# lcd_brd.net
KiCad netlist of a schematic drawn in EAGLE
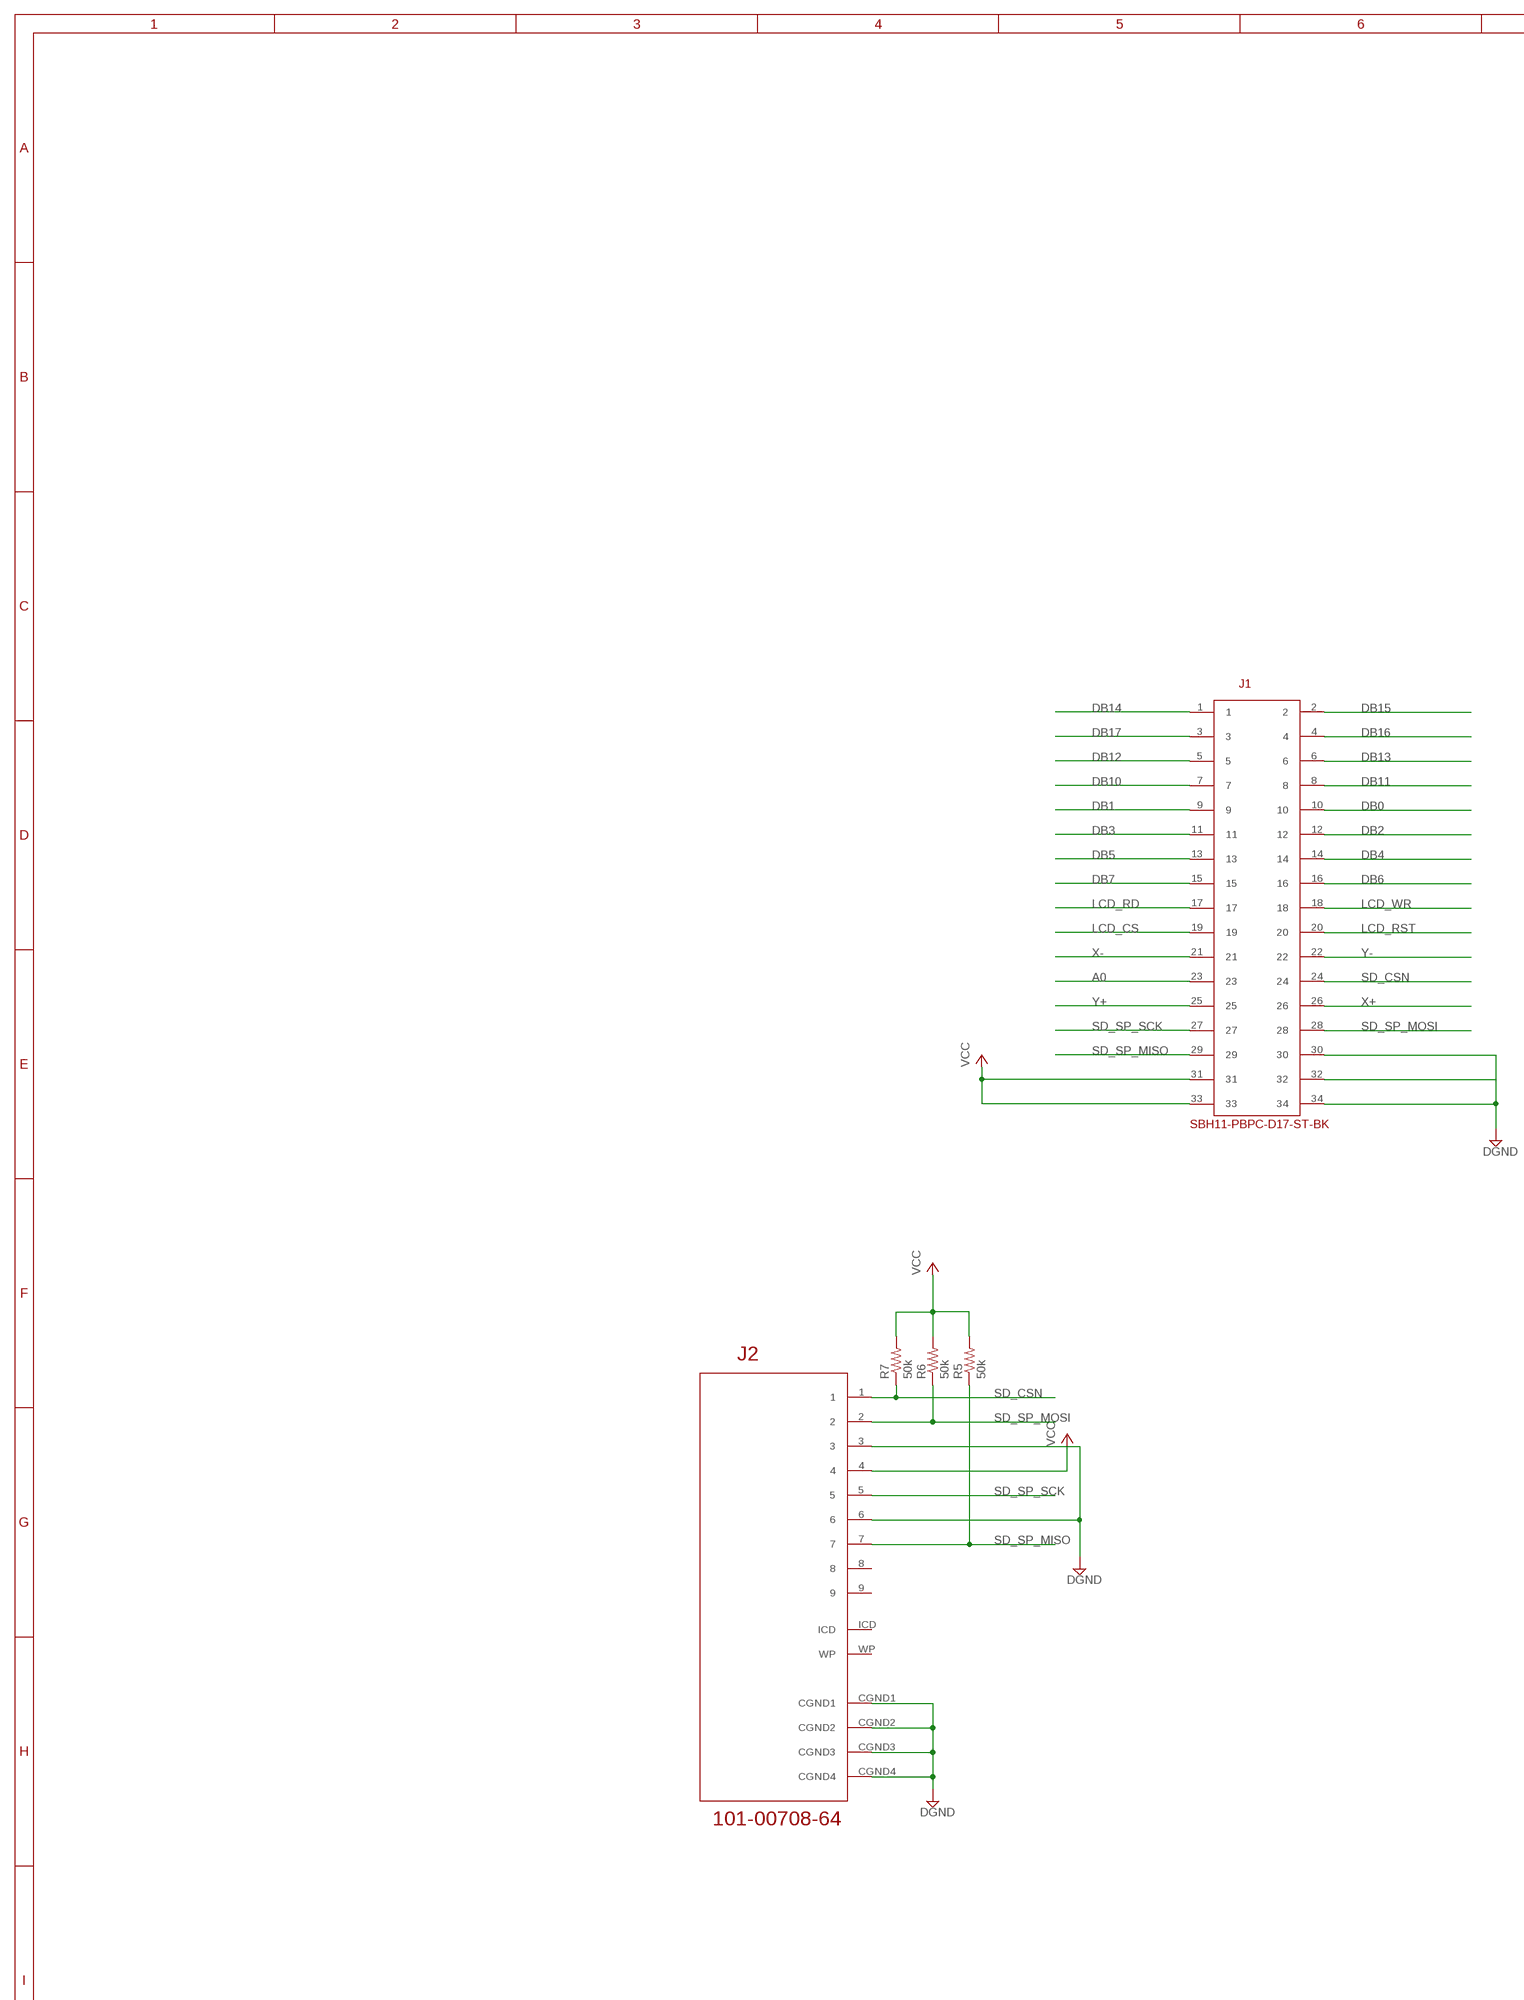
[diagram p0: schematic, sheet 1, part 1 of 2]
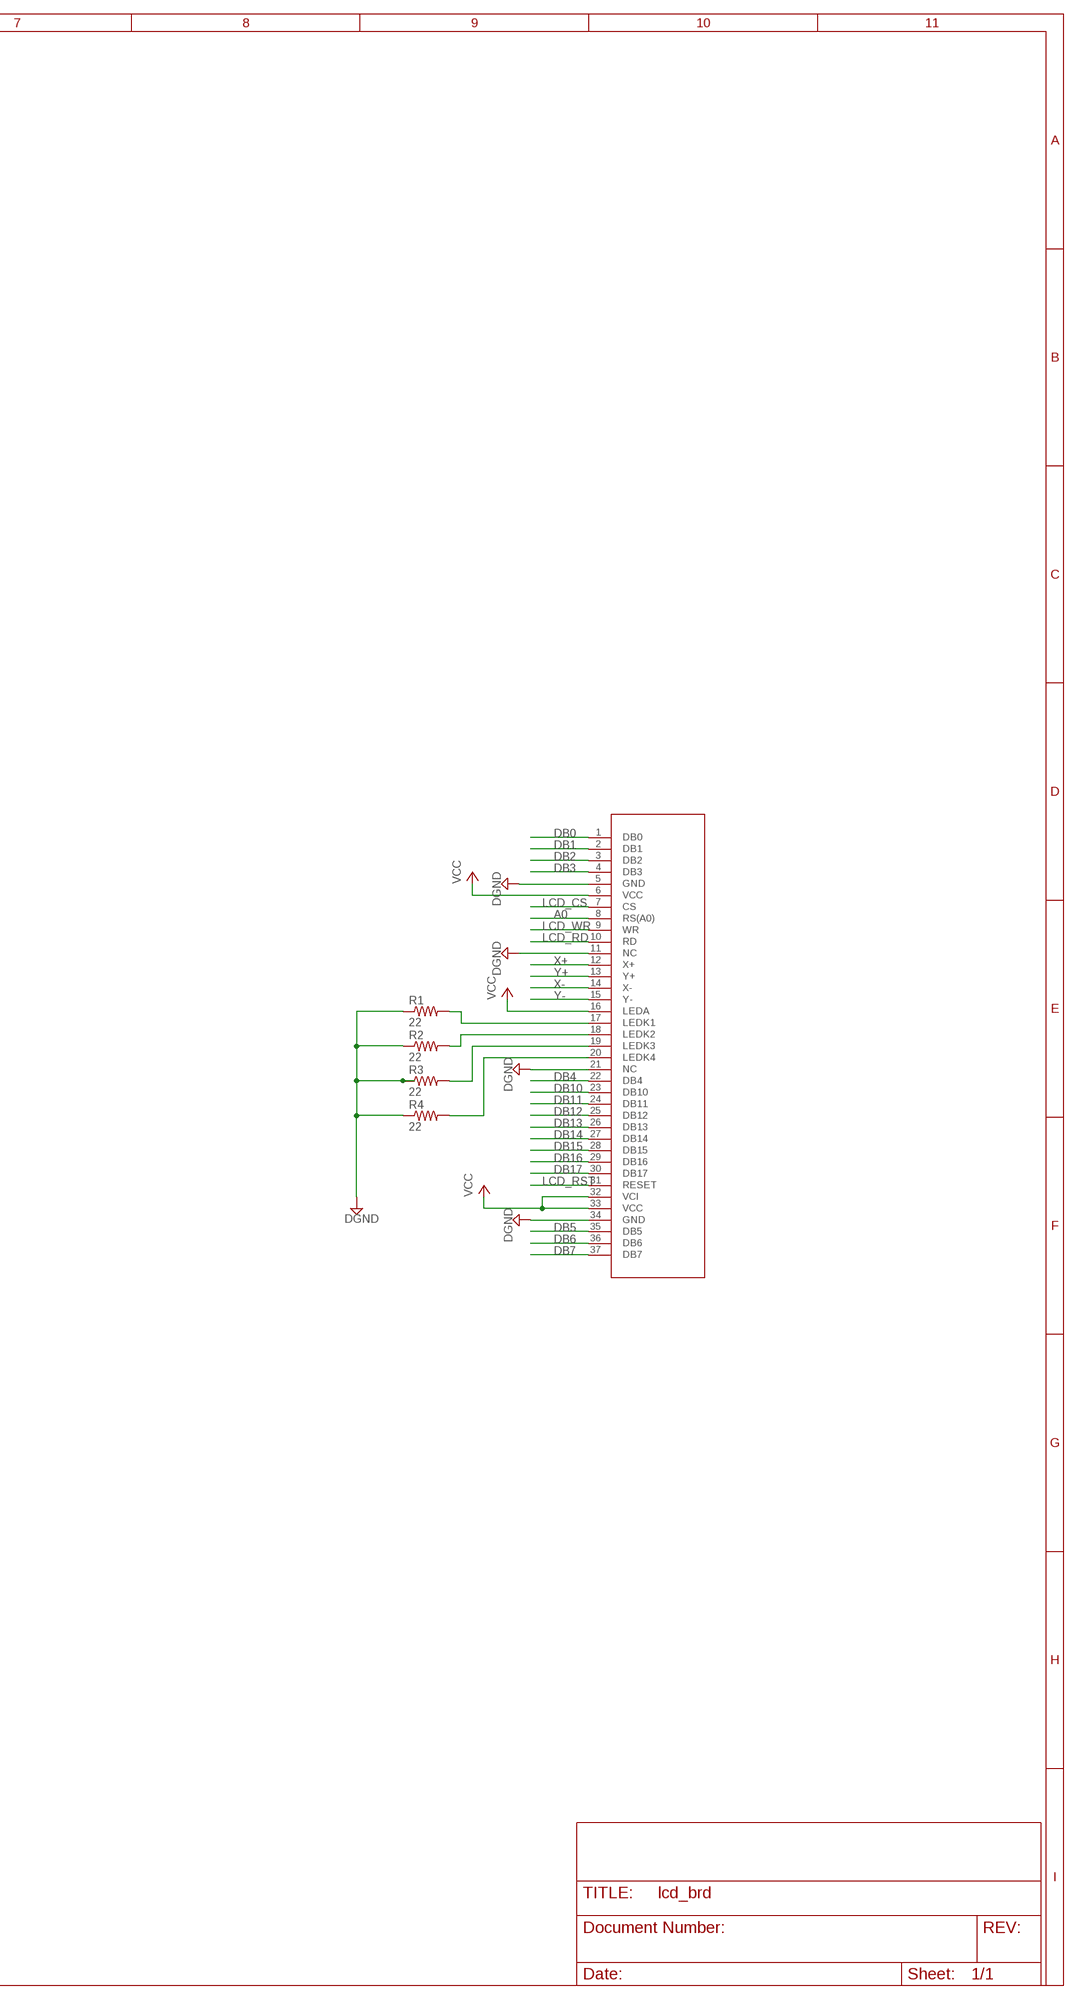
[diagram p1: schematic, sheet 1, part 2 of 2]

(export (version "E")
  (design (tool "Eeschema 10.0.6"))
  (components
    (comp (ref "J1")
      (value "SBH11-PBPC-D17-ST-BK")
      (footprint "eagle-import:SBH11-PBPC-D17-ST-BK")
      (libsource (lib "eagle-import") (part "SBH11-PBPC-D17-ST-BK"))
    )
    (comp (ref "J2")
      (value "101-00708-64")
      (footprint "eagle-import:101-00708-64")
      (libsource (lib "eagle-import") (part "101-00708-64"))
    )
    (comp (ref "R1")
      (value "22")
      (footprint "eagle-import:R0603")
      (libsource (lib "eagle-import") (part "R-US_R0603"))
    )
    (comp (ref "R2")
      (value "22")
      (footprint "eagle-import:R0603")
      (libsource (lib "eagle-import") (part "R-US_R0603"))
    )
    (comp (ref "R3")
      (value "22")
      (footprint "eagle-import:R0603")
      (libsource (lib "eagle-import") (part "R-US_R0603"))
    )
    (comp (ref "R4")
      (value "22")
      (footprint "eagle-import:R0603")
      (libsource (lib "eagle-import") (part "R-US_R0603"))
    )
    (comp (ref "R5")
      (value "50k")
      (footprint "eagle-import:R0603")
      (libsource (lib "eagle-import") (part "R-US_R0603"))
    )
    (comp (ref "R6")
      (value "50k")
      (footprint "eagle-import:R0603")
      (libsource (lib "eagle-import") (part "R-US_R0603"))
    )
    (comp (ref "R7")
      (value "50k")
      (footprint "eagle-import:R0603")
      (libsource (lib "eagle-import") (part "R-US_R0603"))
    )
    (comp (ref "U1")
      (value "PETERATMEGA644_LCD37")
      (footprint "eagle-import:PETERATMEGA644_LCD371MM")
      (libsource (lib "eagle-import") (part "PETERATMEGA644_LCD37"))
    )
  )
  (nets
    (net (code "1") (name "/A0") (class "Default")
      (node (ref "J1") (pin "23") (pinfunction "23_23") (pintype "bidirectional"))
      (node (ref "U1") (pin "8") (pinfunction "RS(A0)_8") (pintype "bidirectional"))
    )
    (net (code "2") (name "/DB0") (class "Default")
      (node (ref "J1") (pin "10") (pinfunction "10_10") (pintype "bidirectional"))
      (node (ref "U1") (pin "1") (pinfunction "DB0_1") (pintype "bidirectional"))
    )
    (net (code "3") (name "/DB1") (class "Default")
      (node (ref "J1") (pin "9") (pinfunction "9_9") (pintype "bidirectional"))
      (node (ref "U1") (pin "2") (pinfunction "DB1_2") (pintype "bidirectional"))
    )
    (net (code "4") (name "/DB2") (class "Default")
      (node (ref "J1") (pin "12") (pinfunction "12_12") (pintype "bidirectional"))
      (node (ref "U1") (pin "3") (pinfunction "DB2_3") (pintype "bidirectional"))
    )
    (net (code "5") (name "/DB3") (class "Default")
      (node (ref "J1") (pin "11") (pinfunction "11_11") (pintype "bidirectional"))
      (node (ref "U1") (pin "4") (pinfunction "DB3_4") (pintype "bidirectional"))
    )
    (net (code "6") (name "/DB4") (class "Default")
      (node (ref "J1") (pin "14") (pinfunction "14_14") (pintype "bidirectional"))
      (node (ref "U1") (pin "22") (pinfunction "DB4_22") (pintype "bidirectional"))
    )
    (net (code "7") (name "/DB5") (class "Default")
      (node (ref "J1") (pin "13") (pinfunction "13_13") (pintype "bidirectional"))
      (node (ref "U1") (pin "35") (pinfunction "DB5_35") (pintype "bidirectional"))
    )
    (net (code "8") (name "/DB6") (class "Default")
      (node (ref "J1") (pin "16") (pinfunction "16_16") (pintype "bidirectional"))
      (node (ref "U1") (pin "36") (pinfunction "DB6_36") (pintype "bidirectional"))
    )
    (net (code "9") (name "/DB7") (class "Default")
      (node (ref "J1") (pin "15") (pinfunction "15_15") (pintype "bidirectional"))
      (node (ref "U1") (pin "37") (pinfunction "DB7_37") (pintype "bidirectional"))
    )
    (net (code "10") (name "/DB10") (class "Default")
      (node (ref "J1") (pin "7") (pinfunction "7_7") (pintype "bidirectional"))
      (node (ref "U1") (pin "23") (pinfunction "DB10_23") (pintype "bidirectional"))
    )
    (net (code "11") (name "/DB11") (class "Default")
      (node (ref "J1") (pin "8") (pinfunction "8_8") (pintype "bidirectional"))
      (node (ref "U1") (pin "24") (pinfunction "DB11_24") (pintype "bidirectional"))
    )
    (net (code "12") (name "/DB12") (class "Default")
      (node (ref "J1") (pin "5") (pinfunction "5_5") (pintype "bidirectional"))
      (node (ref "U1") (pin "25") (pinfunction "DB12_25") (pintype "bidirectional"))
    )
    (net (code "13") (name "/DB13") (class "Default")
      (node (ref "J1") (pin "6") (pinfunction "6_6") (pintype "bidirectional"))
      (node (ref "U1") (pin "26") (pinfunction "DB13_26") (pintype "bidirectional"))
    )
    (net (code "14") (name "/DB14") (class "Default")
      (node (ref "J1") (pin "1") (pinfunction "1_1") (pintype "bidirectional"))
      (node (ref "U1") (pin "27") (pinfunction "DB14_27") (pintype "bidirectional"))
    )
    (net (code "15") (name "/DB15") (class "Default")
      (node (ref "J1") (pin "2") (pinfunction "2_2") (pintype "bidirectional"))
      (node (ref "U1") (pin "28") (pinfunction "DB15_28") (pintype "bidirectional"))
    )
    (net (code "16") (name "/DB16") (class "Default")
      (node (ref "J1") (pin "4") (pinfunction "4_4") (pintype "bidirectional"))
      (node (ref "U1") (pin "29") (pinfunction "DB16_29") (pintype "bidirectional"))
    )
    (net (code "17") (name "/DB17") (class "Default")
      (node (ref "J1") (pin "3") (pinfunction "3_3") (pintype "bidirectional"))
      (node (ref "U1") (pin "30") (pinfunction "DB17_30") (pintype "bidirectional"))
    )
    (net (code "18") (name "/LCD_CS") (class "Default")
      (node (ref "J1") (pin "19") (pinfunction "19_19") (pintype "bidirectional"))
      (node (ref "U1") (pin "7") (pinfunction "CS_7") (pintype "bidirectional"))
    )
    (net (code "19") (name "/LCD_RD") (class "Default")
      (node (ref "J1") (pin "17") (pinfunction "17_17") (pintype "bidirectional"))
      (node (ref "U1") (pin "10") (pinfunction "RD_10") (pintype "bidirectional"))
    )
    (net (code "20") (name "/LCD_RST") (class "Default")
      (node (ref "J1") (pin "20") (pinfunction "20_20") (pintype "bidirectional"))
      (node (ref "U1") (pin "31") (pinfunction "RESET_31") (pintype "bidirectional"))
    )
    (net (code "21") (name "/LCD_WR") (class "Default")
      (node (ref "J1") (pin "18") (pinfunction "18_18") (pintype "bidirectional"))
      (node (ref "U1") (pin "9") (pinfunction "WR_9") (pintype "bidirectional"))
    )
    (net (code "22") (name "/SD_CSN") (class "Default")
      (node (ref "J1") (pin "24") (pinfunction "24_24") (pintype "bidirectional"))
      (node (ref "J2") (pin "1") (pinfunction "1_1") (pintype "bidirectional"))
      (node (ref "R7") (pin "1") (pinfunction "1_1") (pintype "passive"))
    )
    (net (code "23") (name "/SD_SP_MISO") (class "Default")
      (node (ref "J1") (pin "29") (pinfunction "29_29") (pintype "bidirectional"))
      (node (ref "J2") (pin "7") (pinfunction "7_7") (pintype "bidirectional"))
      (node (ref "R5") (pin "1") (pinfunction "1_1") (pintype "passive"))
    )
    (net (code "24") (name "/SD_SP_MOSI") (class "Default")
      (node (ref "J1") (pin "28") (pinfunction "28_28") (pintype "bidirectional"))
      (node (ref "J2") (pin "2") (pinfunction "2_2") (pintype "bidirectional"))
      (node (ref "R6") (pin "1") (pinfunction "1_1") (pintype "passive"))
    )
    (net (code "25") (name "/SD_SP_SCK") (class "Default")
      (node (ref "J1") (pin "27") (pinfunction "27_27") (pintype "bidirectional"))
      (node (ref "J2") (pin "5") (pinfunction "5_5") (pintype "bidirectional"))
    )
    (net (code "26") (name "/X+") (class "Default")
      (node (ref "J1") (pin "26") (pinfunction "26_26") (pintype "bidirectional"))
      (node (ref "U1") (pin "12") (pinfunction "X+_12") (pintype "bidirectional"))
    )
    (net (code "27") (name "/X-") (class "Default")
      (node (ref "J1") (pin "21") (pinfunction "21_21") (pintype "bidirectional"))
      (node (ref "U1") (pin "14") (pinfunction "X-_14") (pintype "bidirectional"))
    )
    (net (code "28") (name "/Y+") (class "Default")
      (node (ref "J1") (pin "25") (pinfunction "25_25") (pintype "bidirectional"))
      (node (ref "U1") (pin "13") (pinfunction "Y+_13") (pintype "bidirectional"))
    )
    (net (code "29") (name "/Y-") (class "Default")
      (node (ref "J1") (pin "22") (pinfunction "22_22") (pintype "bidirectional"))
      (node (ref "U1") (pin "15") (pinfunction "Y-_15") (pintype "bidirectional"))
    )
    (net (code "30") (name "DGND") (class "Default")
      (node (ref "J1") (pin "30") (pinfunction "30_30") (pintype "bidirectional"))
      (node (ref "J1") (pin "32") (pinfunction "32_32") (pintype "bidirectional"))
      (node (ref "J1") (pin "34") (pinfunction "34_34") (pintype "bidirectional"))
      (node (ref "J2") (pin "3") (pinfunction "3_3") (pintype "bidirectional"))
      (node (ref "J2") (pin "6") (pinfunction "6_6") (pintype "bidirectional"))
      (node (ref "J2") (pin "CGND1") (pinfunction "CGND1_CGND1") (pintype "bidirectional"))
      (node (ref "J2") (pin "CGND2") (pinfunction "CGND2_CGND2") (pintype "bidirectional"))
      (node (ref "J2") (pin "CGND3") (pinfunction "CGND3_CGND3") (pintype "bidirectional"))
      (node (ref "J2") (pin "CGND4") (pinfunction "CGND4_CGND4") (pintype "bidirectional"))
      (node (ref "R1") (pin "1") (pinfunction "1_1") (pintype "passive"))
      (node (ref "R2") (pin "1") (pinfunction "1_1") (pintype "passive"))
      (node (ref "R3") (pin "1") (pinfunction "1_1") (pintype "passive"))
      (node (ref "R4") (pin "1") (pinfunction "1_1") (pintype "passive"))
      (node (ref "U1") (pin "11") (pinfunction "NC_11") (pintype "bidirectional"))
      (node (ref "U1") (pin "21") (pinfunction "NC_21") (pintype "bidirectional"))
      (node (ref "U1") (pin "34") (pinfunction "GND_34") (pintype "bidirectional"))
      (node (ref "U1") (pin "5") (pinfunction "GND_5") (pintype "bidirectional"))
    )
    (net (code "31") (name "Net-(U1-LEDK1)") (class "Default")
      (node (ref "R1") (pin "2") (pinfunction "2_2") (pintype "passive"))
      (node (ref "U1") (pin "17") (pinfunction "LEDK1_17") (pintype "bidirectional"))
    )
    (net (code "32") (name "Net-(U1-LEDK2)") (class "Default")
      (node (ref "R2") (pin "2") (pinfunction "2_2") (pintype "passive"))
      (node (ref "U1") (pin "18") (pinfunction "LEDK2_18") (pintype "bidirectional"))
    )
    (net (code "33") (name "Net-(U1-LEDK3)") (class "Default")
      (node (ref "R3") (pin "2") (pinfunction "2_2") (pintype "passive"))
      (node (ref "U1") (pin "19") (pinfunction "LEDK3_19") (pintype "bidirectional"))
    )
    (net (code "34") (name "Net-(U1-LEDK4)") (class "Default")
      (node (ref "R4") (pin "2") (pinfunction "2_2") (pintype "passive"))
      (node (ref "U1") (pin "20") (pinfunction "LEDK4_20") (pintype "bidirectional"))
    )
    (net (code "35") (name "VCC") (class "Default")
      (node (ref "J1") (pin "31") (pinfunction "31_31") (pintype "bidirectional"))
      (node (ref "J1") (pin "33") (pinfunction "33_33") (pintype "bidirectional"))
      (node (ref "J2") (pin "4") (pinfunction "4_4") (pintype "bidirectional"))
      (node (ref "R5") (pin "2") (pinfunction "2_2") (pintype "passive"))
      (node (ref "R6") (pin "2") (pinfunction "2_2") (pintype "passive"))
      (node (ref "R7") (pin "2") (pinfunction "2_2") (pintype "passive"))
      (node (ref "U1") (pin "16") (pinfunction "LEDA_16") (pintype "bidirectional"))
      (node (ref "U1") (pin "32") (pinfunction "VCI_32") (pintype "bidirectional"))
      (node (ref "U1") (pin "33") (pinfunction "VCC_33") (pintype "bidirectional"))
      (node (ref "U1") (pin "6") (pinfunction "VCC_6") (pintype "bidirectional"))
    )
    (net (code "36") (name "unconnected-(J2-Pad8)") (class "Default")
      (node (ref "J2") (pin "8") (pinfunction "8_8") (pintype "bidirectional"))
    )
    (net (code "37") (name "unconnected-(J2-Pad9)") (class "Default")
      (node (ref "J2") (pin "9") (pinfunction "9_9") (pintype "bidirectional"))
    )
    (net (code "38") (name "unconnected-(J2-PadICD)") (class "Default")
      (node (ref "J2") (pin "ICD") (pinfunction "ICD_ICD") (pintype "bidirectional"))
    )
    (net (code "39") (name "unconnected-(J2-PadWP)") (class "Default")
      (node (ref "J2") (pin "WP") (pinfunction "WP_WP") (pintype "bidirectional"))
    )
  )
)
